# Sensor_Board.net
KiCad netlist of a schematic drawn in EAGLE
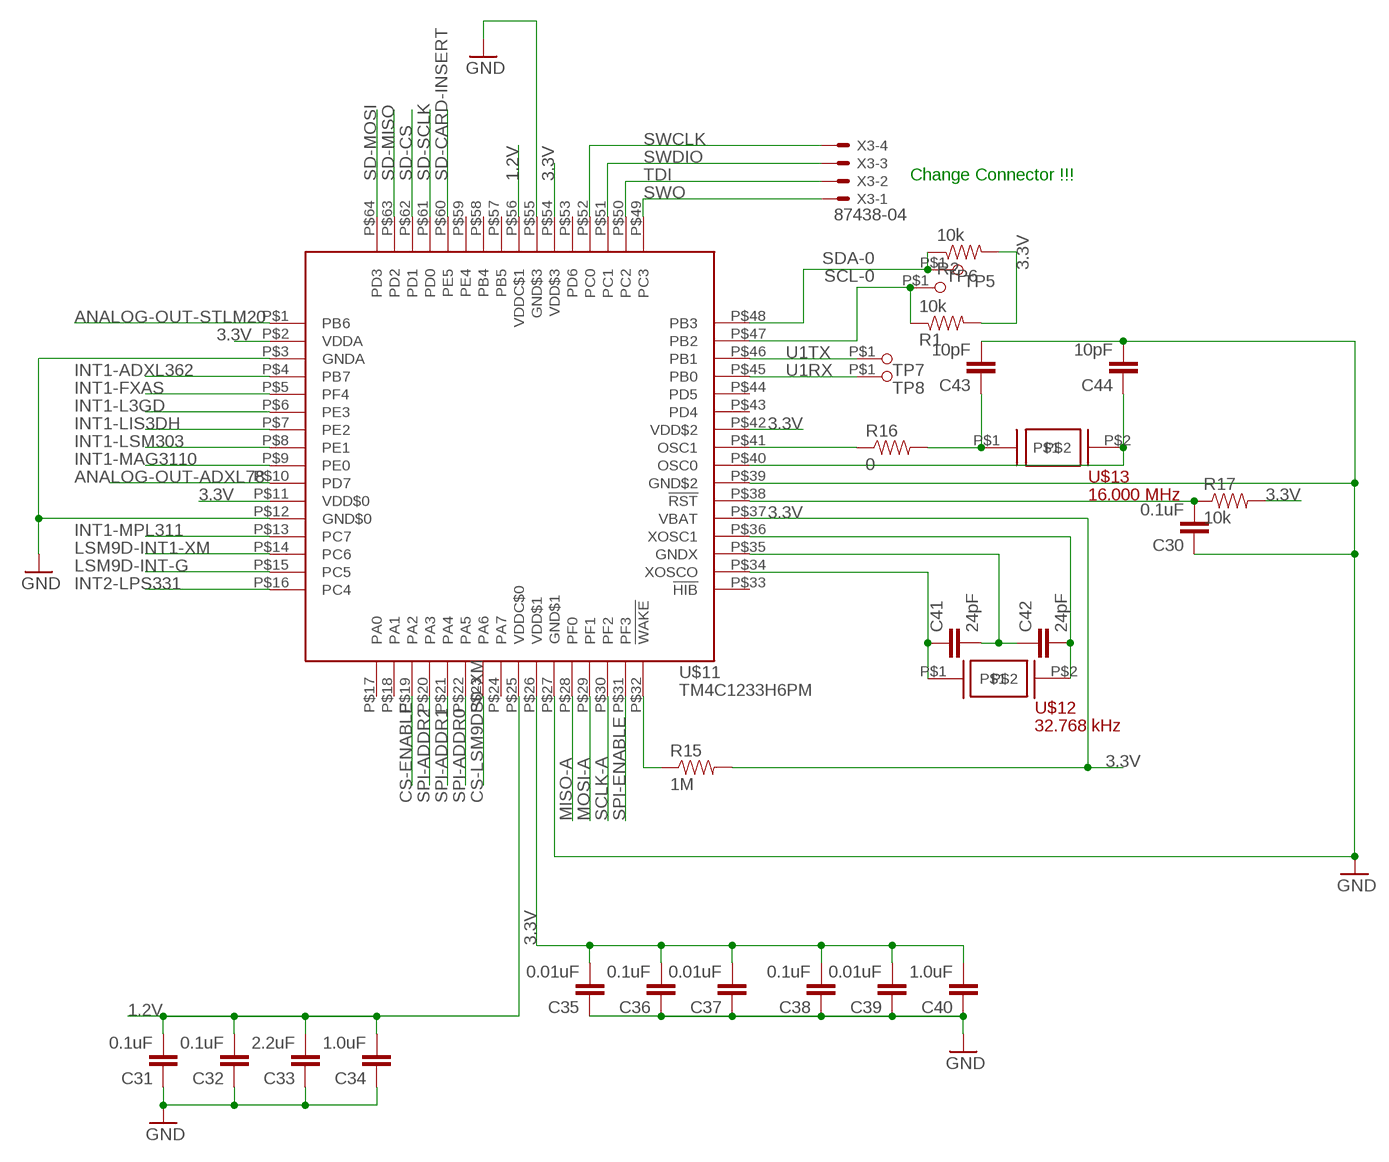
[diagram p0: schematic, sheet 1]
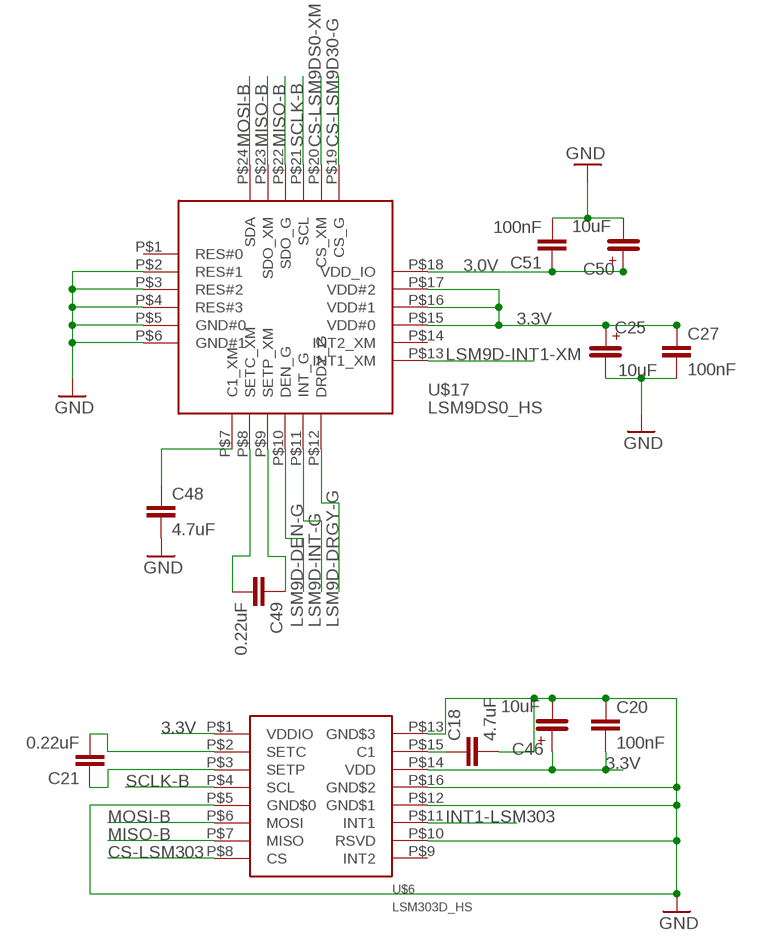
[diagram p1: schematic, sheet 2]
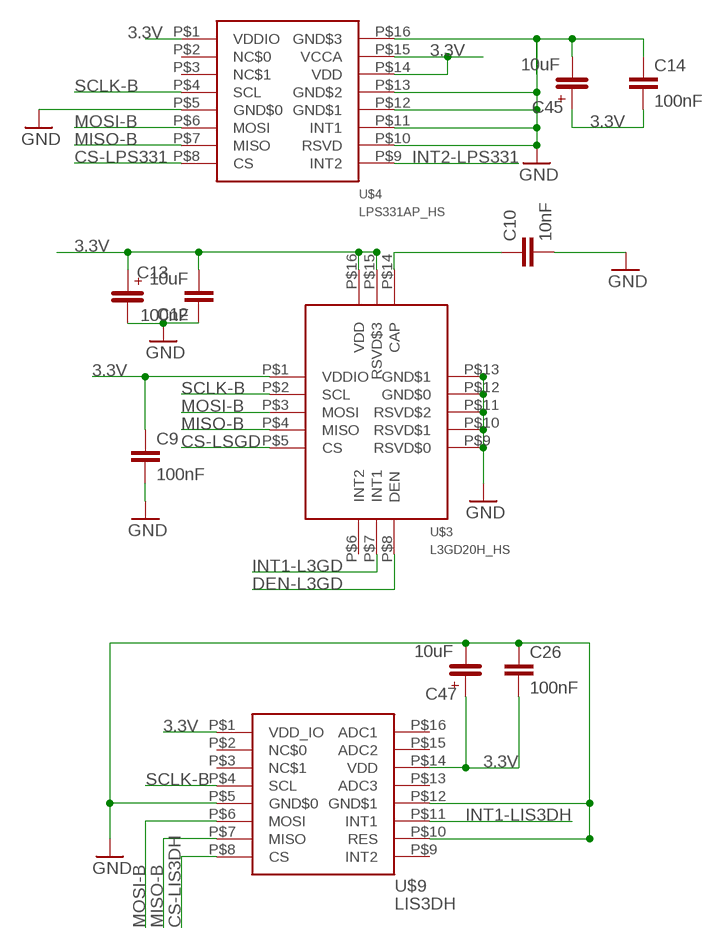
[diagram p2: schematic, sheet 3]
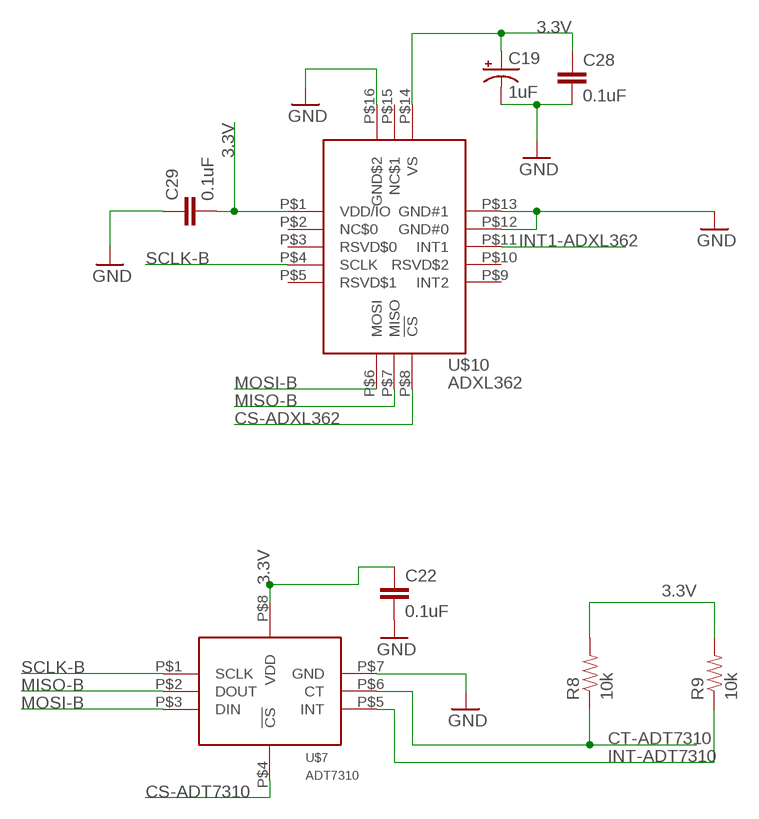
[diagram p3: schematic, sheet 4]
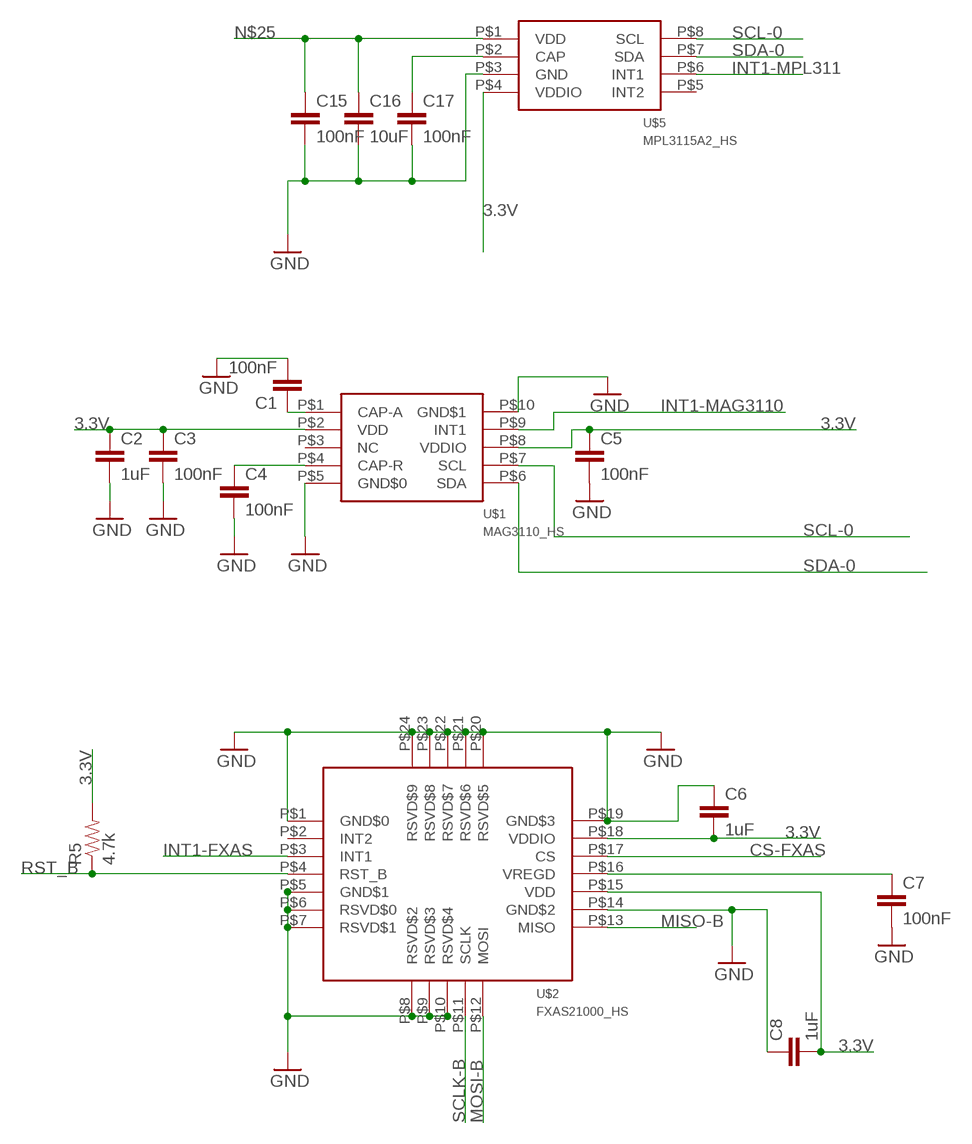
[diagram p4: schematic, sheet 5]
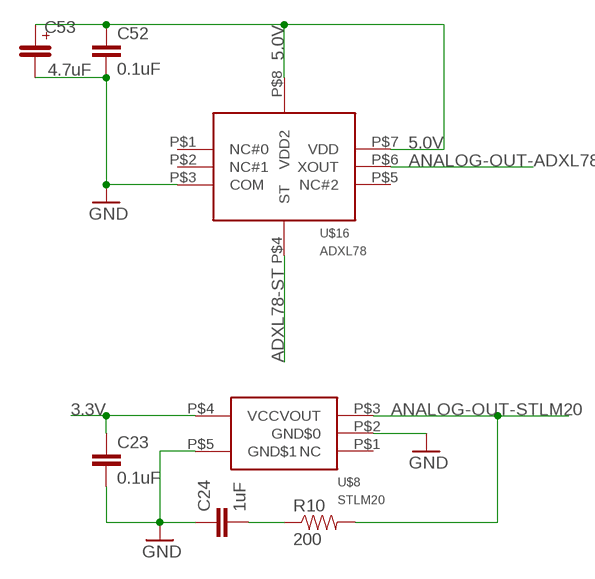
[diagram p5: schematic, sheet 6]
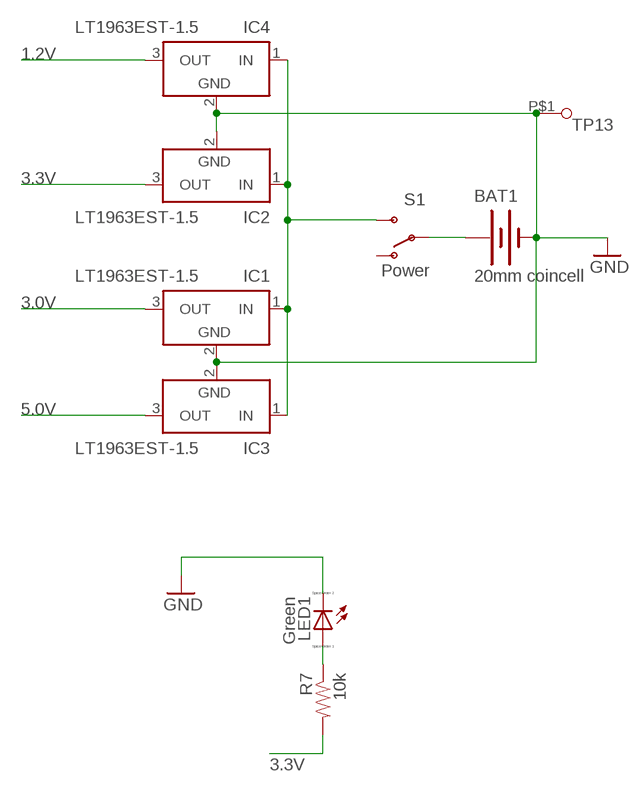
[diagram p6: schematic, sheet 7]
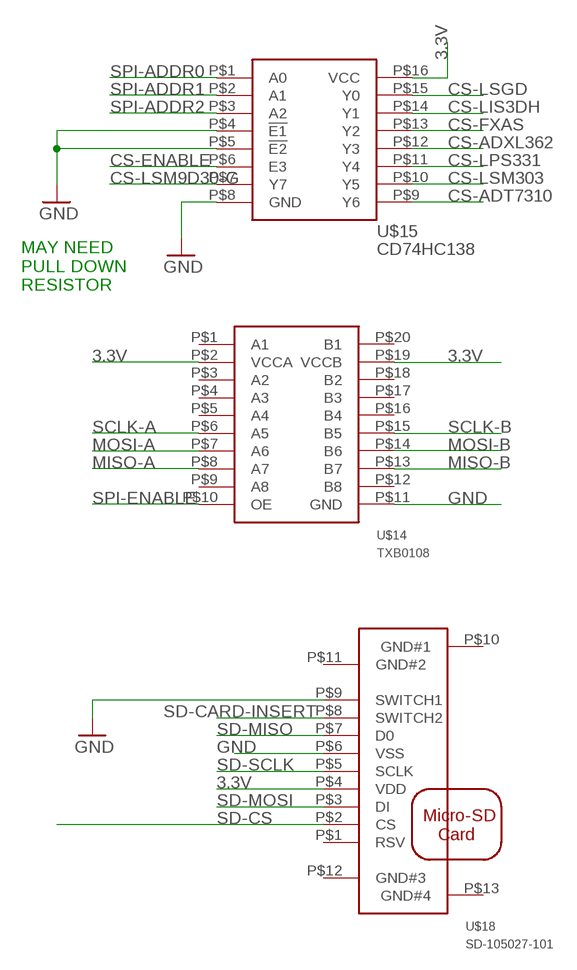
[diagram p7: schematic, sheet 8]

(export (version "E")
  (design (tool "Eeschema 10.0.6"))
  (components
    (comp (ref "C9")
      (value "100nF")
      (footprint "eagle-import:0402-CAP")
      (libsource (lib "eagle-import") (part "CAPACITOR"))
    )
    (comp (ref "C10")
      (value "10nF")
      (footprint "eagle-import:0402-CAP")
      (libsource (lib "eagle-import") (part "CAPACITOR"))
    )
    (comp (ref "C12")
      (value "10uF")
      (footprint "eagle-import:0402-CAP")
      (libsource (lib "eagle-import") (part "CAPACITOR"))
    )
    (comp (ref "C13")
      (value "100nF")
      (footprint "eagle-import:4.3X7.3SMD")
      (libsource (lib "eagle-import") (part "EEFCD0J100ER"))
    )
    (comp (ref "C14")
      (value "100nF")
      (footprint "eagle-import:0402-CAP")
      (libsource (lib "eagle-import") (part "CAPACITOR"))
    )
    (comp (ref "C26")
      (value "100nF")
      (footprint "eagle-import:0402-CAP")
      (libsource (lib "eagle-import") (part "CAPACITOR"))
    )
    (comp (ref "C45")
      (value "10uF")
      (footprint "eagle-import:4.3X7.3SMD")
      (libsource (lib "eagle-import") (part "EEFCD0J100ER"))
    )
    (comp (ref "C47")
      (value "10uF")
      (footprint "eagle-import:4.3X7.3SMD")
      (libsource (lib "eagle-import") (part "EEFCD0J100ER"))
    )
    (comp (ref "U$3")
      (value "L3GD20H_HS")
      (footprint "eagle-import:LGA-16(3X3)_HS")
      (libsource (lib "eagle-import") (part "L3GD20H_HS"))
    )
    (comp (ref "U$4")
      (value "LPS331AP_HS")
      (footprint "eagle-import:LGA-16(3X3)_HS")
      (libsource (lib "eagle-import") (part "LPS331AP_HS"))
    )
    (comp (ref "U$9")
      (value "LIS3DH")
      (footprint "eagle-import:LGA-16(3X3)_HS")
      (libsource (lib "eagle-import") (part "LIS3DH_HS"))
    )
    (comp (ref "BAT1")
      (value "20mm coincell")
      (footprint "eagle-import:BATTCON_20MM_4LEGS")
      (libsource (lib "eagle-import") (part "BATTERY20MM_4LEGS"))
    )
    (comp (ref "IC1")
      (value "LT1963EST-1.5")
      (footprint "eagle-import:SOT223")
      (libsource (lib "eagle-import") (part "LT1963EST-1.5"))
    )
    (comp (ref "IC2")
      (value "LT1963EST-1.5")
      (footprint "eagle-import:SOT223")
      (libsource (lib "eagle-import") (part "LT1963EST-1.5"))
    )
    (comp (ref "IC3")
      (value "LT1963EST-1.5")
      (footprint "eagle-import:SOT223")
      (libsource (lib "eagle-import") (part "LT1963EST-1.5"))
    )
    (comp (ref "IC4")
      (value "LT1963EST-1.5")
      (footprint "eagle-import:SOT223")
      (libsource (lib "eagle-import") (part "LT1963EST-1.5"))
    )
    (comp (ref "LED1")
      (value "Green")
      (footprint "eagle-import:LED_SML0603")
      (libsource (lib "eagle-import") (part "LED_ESML0603"))
    )
    (comp (ref "R7")
      (value "10k")
      (footprint "eagle-import:0402")
      (libsource (lib "eagle-import") (part "RESISTOR"))
    )
    (comp (ref "S1")
      (value "Power")
      (footprint "eagle-import:SWITCH-SPST-SMD-A")
      (libsource (lib "eagle-import") (part "SWITCH-SPDT-SMD-A"))
    )
    (comp (ref "TP13")
      (value "TESTPAD(ROUND)")
      (footprint "eagle-import:TESTPAD(ROUND)")
      (libsource (lib "eagle-import") (part "TESTPAD(ROUND)"))
    )
    (comp (ref "C19")
      (value "1uF")
      (footprint "eagle-import:EIA6032")
      (libsource (lib "eagle-import") (part "CAP_POL6032"))
    )
    (comp (ref "C22")
      (value "0.1uF")
      (footprint "eagle-import:0402-CAP")
      (libsource (lib "eagle-import") (part "CAPACITOR"))
    )
    (comp (ref "C28")
      (value "0.1uF")
      (footprint "eagle-import:0402-CAP")
      (libsource (lib "eagle-import") (part "CAPACITOR"))
    )
    (comp (ref "C29")
      (value "0.1uF")
      (footprint "eagle-import:0402-CAP")
      (libsource (lib "eagle-import") (part "CAPACITOR"))
    )
    (comp (ref "R8")
      (value "10k")
      (footprint "eagle-import:0402")
      (libsource (lib "eagle-import") (part "RESISTOR"))
    )
    (comp (ref "R9")
      (value "10k")
      (footprint "eagle-import:0402")
      (libsource (lib "eagle-import") (part "RESISTOR"))
    )
    (comp (ref "U$7")
      (value "ADT7310")
      (footprint "eagle-import:SOIC-8(5X6.2)")
      (libsource (lib "eagle-import") (part "ADT7310"))
    )
    (comp (ref "U$10")
      (value "ADXL362")
      (footprint "eagle-import:LGA-16(3X3.25)_HS")
      (libsource (lib "eagle-import") (part "ADXL362_HS"))
    )
    (comp (ref "C30")
      (value "0.1uF")
      (footprint "eagle-import:0402-CAP")
      (libsource (lib "eagle-import") (part "CAPACITOR"))
    )
    (comp (ref "C31")
      (value "0.1uF")
      (footprint "eagle-import:0402-CAP")
      (libsource (lib "eagle-import") (part "CAPACITOR"))
    )
    (comp (ref "C32")
      (value "0.1uF")
      (footprint "eagle-import:0402-CAP")
      (libsource (lib "eagle-import") (part "CAPACITOR"))
    )
    (comp (ref "C33")
      (value "2.2uF")
      (footprint "eagle-import:0402-CAP")
      (libsource (lib "eagle-import") (part "CAPACITOR"))
    )
    (comp (ref "C34")
      (value "1.0uF")
      (footprint "eagle-import:0402-CAP")
      (libsource (lib "eagle-import") (part "CAPACITOR"))
    )
    (comp (ref "C35")
      (value "0.01uF")
      (footprint "eagle-import:0402-CAP")
      (libsource (lib "eagle-import") (part "CAPACITOR"))
    )
    (comp (ref "C36")
      (value "0.1uF")
      (footprint "eagle-import:0402-CAP")
      (libsource (lib "eagle-import") (part "CAPACITOR"))
    )
    (comp (ref "C37")
      (value "0.01uF")
      (footprint "eagle-import:0402-CAP")
      (libsource (lib "eagle-import") (part "CAPACITOR"))
    )
    (comp (ref "C38")
      (value "0.1uF")
      (footprint "eagle-import:0402-CAP")
      (libsource (lib "eagle-import") (part "CAPACITOR"))
    )
    (comp (ref "C39")
      (value "0.01uF")
      (footprint "eagle-import:0402-CAP")
      (libsource (lib "eagle-import") (part "CAPACITOR"))
    )
    (comp (ref "C40")
      (value "1.0uF")
      (footprint "eagle-import:0402-CAP")
      (libsource (lib "eagle-import") (part "CAPACITOR"))
    )
    (comp (ref "C41")
      (value "24pF")
      (footprint "eagle-import:0402-CAP")
      (libsource (lib "eagle-import") (part "CAPACITOR"))
    )
    (comp (ref "C42")
      (value "24pF")
      (footprint "eagle-import:0402-CAP")
      (libsource (lib "eagle-import") (part "CAPACITOR"))
    )
    (comp (ref "C43")
      (value "10pF")
      (footprint "eagle-import:0402-CAP")
      (libsource (lib "eagle-import") (part "CAPACITOR"))
    )
    (comp (ref "C44")
      (value "10pF")
      (footprint "eagle-import:0402-CAP")
      (libsource (lib "eagle-import") (part "CAPACITOR"))
    )
    (comp (ref "R1")
      (value "10k")
      (footprint "eagle-import:0402")
      (libsource (lib "eagle-import") (part "RESISTOR"))
    )
    (comp (ref "R2")
      (value "10k")
      (footprint "eagle-import:0402")
      (libsource (lib "eagle-import") (part "RESISTOR"))
    )
    (comp (ref "R15")
      (value "1M")
      (footprint "eagle-import:0402")
      (libsource (lib "eagle-import") (part "RESISTOR"))
    )
    (comp (ref "R16")
      (value "0")
      (footprint "eagle-import:0402")
      (libsource (lib "eagle-import") (part "RESISTOR"))
    )
    (comp (ref "R17")
      (value "10k")
      (footprint "eagle-import:0402")
      (libsource (lib "eagle-import") (part "RESISTOR"))
    )
    (comp (ref "TP5")
      (value "TESTPAD(ROUND)")
      (footprint "eagle-import:TESTPAD(ROUND)")
      (libsource (lib "eagle-import") (part "TESTPAD(ROUND)"))
    )
    (comp (ref "TP6")
      (value "TESTPAD(ROUND)")
      (footprint "eagle-import:TESTPAD(ROUND)")
      (libsource (lib "eagle-import") (part "TESTPAD(ROUND)"))
    )
    (comp (ref "TP7")
      (value "TESTPAD(ROUND)")
      (footprint "eagle-import:TESTPAD(ROUND)")
      (libsource (lib "eagle-import") (part "TESTPAD(ROUND)"))
    )
    (comp (ref "TP8")
      (value "TESTPAD(ROUND)")
      (footprint "eagle-import:TESTPAD(ROUND)")
      (libsource (lib "eagle-import") (part "TESTPAD(ROUND)"))
    )
    (comp (ref "U$11")
      (value "TM4C1233H6PM")
      (footprint "eagle-import:S-PQFP-G64")
      (libsource (lib "eagle-import") (part "TM4C1233H6PM"))
    )
    (comp (ref "U$12")
      (value "32.768 kHz")
      (footprint "eagle-import:CYLINDRICAL-(1.9DIAX6L)")
      (libsource (lib "eagle-import") (part "AB26TRB"))
    )
    (comp (ref "U$13")
      (value "16.000 MHz")
      (footprint "eagle-import:2-SMD")
      (libsource (lib "eagle-import") (part "NX5032GA"))
    )
    (comp (ref "X3")
      (value "87438-04")
      (footprint "eagle-import:87438-04")
      (libsource (lib "eagle-import") (part "87438-04"))
    )
    (comp (ref "C18")
      (value "4.7uF")
      (footprint "eagle-import:0402-CAP")
      (libsource (lib "eagle-import") (part "CAPACITOR"))
    )
    (comp (ref "C20")
      (value "100nF")
      (footprint "eagle-import:0402-CAP")
      (libsource (lib "eagle-import") (part "CAPACITOR"))
    )
    (comp (ref "C21")
      (value "0.22uF")
      (footprint "eagle-import:0402-CAP")
      (libsource (lib "eagle-import") (part "CAPACITOR"))
    )
    (comp (ref "C25")
      (value "10uF")
      (footprint "eagle-import:4.3X7.3SMD")
      (libsource (lib "eagle-import") (part "EEFCD0J100ER"))
    )
    (comp (ref "C27")
      (value "100nF")
      (footprint "eagle-import:0402-CAP")
      (libsource (lib "eagle-import") (part "CAPACITOR"))
    )
    (comp (ref "C46")
      (value "10uF")
      (footprint "eagle-import:4.3X7.3SMD")
      (libsource (lib "eagle-import") (part "EEFCD0J100ER"))
    )
    (comp (ref "C48")
      (value "4.7uF")
      (footprint "eagle-import:0402-CAP")
      (libsource (lib "eagle-import") (part "CAPACITOR"))
    )
    (comp (ref "C49")
      (value "0.22uF")
      (footprint "eagle-import:0402-CAP")
      (libsource (lib "eagle-import") (part "CAPACITOR"))
    )
    (comp (ref "C50")
      (value "10uF")
      (footprint "eagle-import:4.3X7.3SMD")
      (libsource (lib "eagle-import") (part "EEFCD0J100ER"))
    )
    (comp (ref "C51")
      (value "100nF")
      (footprint "eagle-import:0402-CAP")
      (libsource (lib "eagle-import") (part "CAPACITOR"))
    )
    (comp (ref "U$6")
      (value "LSM303D_HS")
      (footprint "eagle-import:LGA-16(3X3)_HS")
      (libsource (lib "eagle-import") (part "LSM303D_HS"))
    )
    (comp (ref "U$17")
      (value "LSM9DS0_HS")
      (footprint "eagle-import:LGA-24(4X4)_HS")
      (libsource (lib "eagle-import") (part "LSM9DS0_HS"))
    )
    (comp (ref "C23")
      (value "0.1uF")
      (footprint "eagle-import:0402-CAP")
      (libsource (lib "eagle-import") (part "CAPACITOR"))
    )
    (comp (ref "C24")
      (value "1uF")
      (footprint "eagle-import:0402-CAP")
      (libsource (lib "eagle-import") (part "CAPACITOR"))
    )
    (comp (ref "C52")
      (value "0.1uF")
      (footprint "eagle-import:0402-CAP")
      (libsource (lib "eagle-import") (part "CAPACITOR"))
    )
    (comp (ref "C53")
      (value "4.7uF")
      (footprint "eagle-import:4.3X7.3SMD")
      (libsource (lib "eagle-import") (part "EEFCD0J100ER"))
    )
    (comp (ref "R10")
      (value "200")
      (footprint "eagle-import:0402")
      (libsource (lib "eagle-import") (part "RESISTOR"))
    )
    (comp (ref "U$8")
      (value "STLM20")
      (footprint "eagle-import:SOT323-5L")
      (libsource (lib "eagle-import") (part "STLM20"))
    )
    (comp (ref "U$16")
      (value "ADXL78")
      (footprint "eagle-import:LCC-8(5X5)_HS")
      (libsource (lib "eagle-import") (part "ADXL78"))
    )
    (comp (ref "C1")
      (value "100nF")
      (footprint "eagle-import:0402-CAP")
      (libsource (lib "eagle-import") (part "CAPACITOR"))
    )
    (comp (ref "C2")
      (value "1uF")
      (footprint "eagle-import:0402-CAP")
      (libsource (lib "eagle-import") (part "CAPACITOR"))
    )
    (comp (ref "C3")
      (value "100nF")
      (footprint "eagle-import:0402-CAP")
      (libsource (lib "eagle-import") (part "CAPACITOR"))
    )
    (comp (ref "C4")
      (value "100nF")
      (footprint "eagle-import:0402-CAP")
      (libsource (lib "eagle-import") (part "CAPACITOR"))
    )
    (comp (ref "C5")
      (value "100nF")
      (footprint "eagle-import:0402-CAP")
      (libsource (lib "eagle-import") (part "CAPACITOR"))
    )
    (comp (ref "C6")
      (value "1uF")
      (footprint "eagle-import:0402-CAP")
      (libsource (lib "eagle-import") (part "CAPACITOR"))
    )
    (comp (ref "C7")
      (value "100nF")
      (footprint "eagle-import:0402-CAP")
      (libsource (lib "eagle-import") (part "CAPACITOR"))
    )
    (comp (ref "C8")
      (value "1uF")
      (footprint "eagle-import:0402-CAP")
      (libsource (lib "eagle-import") (part "CAPACITOR"))
    )
    (comp (ref "C15")
      (value "100nF")
      (footprint "eagle-import:0402-CAP")
      (libsource (lib "eagle-import") (part "CAPACITOR"))
    )
    (comp (ref "C16")
      (value "10uF")
      (footprint "eagle-import:0402-CAP")
      (libsource (lib "eagle-import") (part "CAPACITOR"))
    )
    (comp (ref "C17")
      (value "100nF")
      (footprint "eagle-import:0402-CAP")
      (libsource (lib "eagle-import") (part "CAPACITOR"))
    )
    (comp (ref "R5")
      (value "4.7k")
      (footprint "eagle-import:0402")
      (libsource (lib "eagle-import") (part "RESISTOR"))
    )
    (comp (ref "U$1")
      (value "MAG3110_HS")
      (footprint "eagle-import:DFN-10(2X2)_HS")
      (libsource (lib "eagle-import") (part "MAG3110_HS"))
    )
    (comp (ref "U$2")
      (value "FXAS21000_HS")
      (footprint "eagle-import:QFN-24(4X4)_HS")
      (libsource (lib "eagle-import") (part "FXAS21000_HS"))
    )
    (comp (ref "U$5")
      (value "MPL3115A2_HS")
      (footprint "eagle-import:LGA-8(5X3)_HS")
      (libsource (lib "eagle-import") (part "MPL3115A2_HS"))
    )
    (comp (ref "U$14")
      (value "TXB0108")
      (footprint "eagle-import:TSSOP-(PW)-20")
      (libsource (lib "eagle-import") (part "TXB0108"))
    )
    (comp (ref "U$15")
      (value "CD74HC138")
      (footprint "eagle-import:SOIC-16")
      (libsource (lib "eagle-import") (part "CD74HC138"))
    )
    (comp (ref "U$18")
      (value "SD-105027-101")
      (footprint "eagle-import:SD-105027-101")
      (libsource (lib "eagle-import") (part "SD-105027-101"))
    )
  )
  (nets
    (net (code "1") (name "1.2V") (class "Default")
      (node (ref "C31") (pin "2") (pinfunction "2_2") (pintype "passive"))
      (node (ref "C32") (pin "2") (pinfunction "2_2") (pintype "passive"))
      (node (ref "C33") (pin "2") (pinfunction "2_2") (pintype "passive"))
      (node (ref "C34") (pin "2") (pinfunction "2_2") (pintype "passive"))
      (node (ref "IC4") (pin "3") (pinfunction "OUT_3") (pintype "output"))
      (node (ref "U$11") (pin "P$25") (pinfunction "VDDC$0_P$25") (pintype "bidirectional"))
      (node (ref "U$11") (pin "P$56") (pinfunction "VDDC$1_P$56") (pintype "bidirectional"))
    )
    (net (code "2") (name "3.0V") (class "Default")
      (node (ref "C50") (pin "P$1") (pintype "bidirectional"))
      (node (ref "C51") (pin "1") (pinfunction "1_1") (pintype "passive"))
      (node (ref "IC1") (pin "3") (pinfunction "OUT_3") (pintype "output"))
      (node (ref "U$17") (pin "P$18") (pinfunction "VDD_IO_P$18") (pintype "bidirectional"))
    )
    (net (code "3") (name "3.3V") (class "Default")
      (node (ref "C12") (pin "2") (pinfunction "2_2") (pintype "passive"))
      (node (ref "C13") (pin "P$1") (pintype "bidirectional"))
      (node (ref "C14") (pin "2") (pinfunction "2_2") (pintype "passive"))
      (node (ref "C19") (pin "P$1") (pinfunction "+_P$1") (pintype "passive"))
      (node (ref "C2") (pin "1") (pinfunction "1_1") (pintype "passive"))
      (node (ref "C20") (pin "2") (pinfunction "2_2") (pintype "passive"))
      (node (ref "C22") (pin "1") (pinfunction "1_1") (pintype "passive"))
      (node (ref "C23") (pin "1") (pinfunction "1_1") (pintype "passive"))
      (node (ref "C25") (pin "P$1") (pintype "bidirectional"))
      (node (ref "C26") (pin "2") (pinfunction "2_2") (pintype "passive"))
      (node (ref "C27") (pin "1") (pinfunction "1_1") (pintype "passive"))
      (node (ref "C28") (pin "1") (pinfunction "1_1") (pintype "passive"))
      (node (ref "C29") (pin "2") (pinfunction "2_2") (pintype "passive"))
      (node (ref "C3") (pin "1") (pinfunction "1_1") (pintype "passive"))
      (node (ref "C35") (pin "2") (pinfunction "2_2") (pintype "passive"))
      (node (ref "C36") (pin "2") (pinfunction "2_2") (pintype "passive"))
      (node (ref "C37") (pin "2") (pinfunction "2_2") (pintype "passive"))
      (node (ref "C38") (pin "2") (pinfunction "2_2") (pintype "passive"))
      (node (ref "C39") (pin "2") (pinfunction "2_2") (pintype "passive"))
      (node (ref "C40") (pin "2") (pinfunction "2_2") (pintype "passive"))
      (node (ref "C45") (pin "P$1") (pintype "bidirectional"))
      (node (ref "C46") (pin "P$1") (pintype "bidirectional"))
      (node (ref "C47") (pin "P$1") (pintype "bidirectional"))
      (node (ref "C5") (pin "1") (pinfunction "1_1") (pintype "passive"))
      (node (ref "C6") (pin "2") (pinfunction "2_2") (pintype "passive"))
      (node (ref "C8") (pin "2") (pinfunction "2_2") (pintype "passive"))
      (node (ref "C9") (pin "1") (pinfunction "1_1") (pintype "passive"))
      (node (ref "IC2") (pin "3") (pinfunction "OUT_3") (pintype "output"))
      (node (ref "R1") (pin "2") (pinfunction "2_2") (pintype "passive"))
      (node (ref "R15") (pin "2") (pinfunction "2_2") (pintype "passive"))
      (node (ref "R17") (pin "2") (pinfunction "2_2") (pintype "passive"))
      (node (ref "R2") (pin "2") (pinfunction "2_2") (pintype "passive"))
      (node (ref "R5") (pin "2") (pinfunction "2_2") (pintype "passive"))
      (node (ref "R7") (pin "2") (pinfunction "2_2") (pintype "passive"))
      (node (ref "R8") (pin "2") (pinfunction "2_2") (pintype "passive"))
      (node (ref "R9") (pin "2") (pinfunction "2_2") (pintype "passive"))
      (node (ref "U$1") (pin "P$2") (pinfunction "VDD_P$2") (pintype "bidirectional"))
      (node (ref "U$1") (pin "P$8") (pinfunction "VDDIO_P$8") (pintype "bidirectional"))
      (node (ref "U$10") (pin "P$1") (pinfunction "VDD/IO_P$1") (pintype "bidirectional"))
      (node (ref "U$10") (pin "P$14") (pinfunction "VS_P$14") (pintype "bidirectional"))
      (node (ref "U$11") (pin "P$11") (pinfunction "VDD$0_P$11") (pintype "bidirectional"))
      (node (ref "U$11") (pin "P$2") (pinfunction "VDDA_P$2") (pintype "bidirectional"))
      (node (ref "U$11") (pin "P$26") (pinfunction "VDD$1_P$26") (pintype "bidirectional"))
      (node (ref "U$11") (pin "P$37") (pinfunction "VBAT_P$37") (pintype "bidirectional"))
      (node (ref "U$11") (pin "P$42") (pinfunction "VDD$2_P$42") (pintype "bidirectional"))
      (node (ref "U$11") (pin "P$54") (pinfunction "VDD$3_P$54") (pintype "bidirectional"))
      (node (ref "U$14") (pin "P$19") (pinfunction "VCCB_P$19") (pintype "bidirectional"))
      (node (ref "U$14") (pin "P$2") (pinfunction "VCCA_P$2") (pintype "bidirectional"))
      (node (ref "U$15") (pin "P$16") (pinfunction "VCC_P$16") (pintype "bidirectional"))
      (node (ref "U$17") (pin "P$15") (pinfunction "VDD#0_P$15") (pintype "bidirectional"))
      (node (ref "U$17") (pin "P$16") (pinfunction "VDD#1_P$16") (pintype "bidirectional"))
      (node (ref "U$17") (pin "P$17") (pinfunction "VDD#2_P$17") (pintype "bidirectional"))
      (node (ref "U$18") (pin "P$4") (pinfunction "VDD_P$4") (pintype "bidirectional"))
      (node (ref "U$2") (pin "P$15") (pinfunction "VDD_P$15") (pintype "bidirectional"))
      (node (ref "U$2") (pin "P$18") (pinfunction "VDDIO_P$18") (pintype "bidirectional"))
      (node (ref "U$3") (pin "P$1") (pinfunction "VDDIO_P$1") (pintype "bidirectional"))
      (node (ref "U$3") (pin "P$15") (pinfunction "RSVD$3_P$15") (pintype "bidirectional"))
      (node (ref "U$3") (pin "P$16") (pinfunction "VDD_P$16") (pintype "bidirectional"))
      (node (ref "U$4") (pin "P$1") (pinfunction "VDDIO_P$1") (pintype "bidirectional"))
      (node (ref "U$4") (pin "P$14") (pinfunction "VDD_P$14") (pintype "bidirectional"))
      (node (ref "U$4") (pin "P$15") (pinfunction "VCCA_P$15") (pintype "bidirectional"))
      (node (ref "U$5") (pin "P$4") (pinfunction "VDDIO_P$4") (pintype "bidirectional"))
      (node (ref "U$6") (pin "P$1") (pinfunction "VDDIO_P$1") (pintype "bidirectional"))
      (node (ref "U$6") (pin "P$14") (pinfunction "VDD_P$14") (pintype "bidirectional"))
      (node (ref "U$7") (pin "P$8") (pinfunction "VDD_P$8") (pintype "bidirectional"))
      (node (ref "U$8") (pin "P$4") (pinfunction "VCC_P$4") (pintype "bidirectional"))
      (node (ref "U$9") (pin "P$1") (pinfunction "VDD_IO_P$1") (pintype "bidirectional"))
      (node (ref "U$9") (pin "P$14") (pinfunction "VDD_P$14") (pintype "bidirectional"))
    )
    (net (code "4") (name "5.0V") (class "Default")
      (node (ref "C52") (pin "1") (pinfunction "1_1") (pintype "passive"))
      (node (ref "C53") (pin "P$1") (pintype "bidirectional"))
      (node (ref "IC3") (pin "3") (pinfunction "OUT_3") (pintype "output"))
      (node (ref "U$16") (pin "P$7") (pinfunction "VDD_P$7") (pintype "bidirectional"))
      (node (ref "U$16") (pin "P$8") (pinfunction "VDD2_P$8") (pintype "bidirectional"))
    )
    (net (code "5") (name "ADXL78-ST") (class "Default")
      (node (ref "U$16") (pin "P$4") (pinfunction "ST_P$4") (pintype "bidirectional"))
    )
    (net (code "6") (name "ANALOG-OUT-ADXL78") (class "Default")
      (node (ref "U$11") (pin "P$10") (pinfunction "PD7_P$10") (pintype "bidirectional"))
      (node (ref "U$16") (pin "P$6") (pinfunction "XOUT_P$6") (pintype "bidirectional"))
    )
    (net (code "7") (name "ANALOG-OUT-STLM20") (class "Default")
      (node (ref "R10") (pin "2") (pinfunction "2_2") (pintype "passive"))
      (node (ref "U$11") (pin "P$1") (pinfunction "PB6_P$1") (pintype "bidirectional"))
      (node (ref "U$8") (pin "P$3") (pinfunction "VOUT_P$3") (pintype "bidirectional"))
    )
    (net (code "8") (name "CS-ADT7310") (class "Default")
      (node (ref "U$15") (pin "P$9") (pinfunction "Y6_P$9") (pintype "bidirectional"))
      (node (ref "U$7") (pin "P$4") (pinfunction "~{CS}_P$4") (pintype "bidirectional"))
    )
    (net (code "9") (name "CS-ADXL362") (class "Default")
      (node (ref "U$10") (pin "P$8") (pinfunction "~{CS}_P$8") (pintype "bidirectional"))
      (node (ref "U$15") (pin "P$12") (pinfunction "Y3_P$12") (pintype "bidirectional"))
    )
    (net (code "10") (name "CS-ENABLE") (class "Default")
      (node (ref "U$11") (pin "P$19") (pinfunction "PA2_P$19") (pintype "bidirectional"))
      (node (ref "U$15") (pin "P$6") (pinfunction "E3_P$6") (pintype "bidirectional"))
    )
    (net (code "11") (name "CS-FXAS") (class "Default")
      (node (ref "U$15") (pin "P$13") (pinfunction "Y2_P$13") (pintype "bidirectional"))
      (node (ref "U$2") (pin "P$17") (pinfunction "CS_P$17") (pintype "bidirectional"))
    )
    (net (code "12") (name "CS-LIS3DH") (class "Default")
      (node (ref "U$15") (pin "P$14") (pinfunction "Y1_P$14") (pintype "bidirectional"))
      (node (ref "U$9") (pin "P$8") (pinfunction "CS_P$8") (pintype "bidirectional"))
    )
    (net (code "13") (name "CS-LPS331") (class "Default")
      (node (ref "U$15") (pin "P$11") (pinfunction "Y4_P$11") (pintype "bidirectional"))
      (node (ref "U$4") (pin "P$8") (pinfunction "CS_P$8") (pintype "bidirectional"))
    )
    (net (code "14") (name "CS-LSGD") (class "Default")
      (node (ref "U$15") (pin "P$15") (pinfunction "Y0_P$15") (pintype "bidirectional"))
      (node (ref "U$3") (pin "P$5") (pinfunction "CS_P$5") (pintype "bidirectional"))
    )
    (net (code "15") (name "CS-LSM9D30-G") (class "Default")
      (node (ref "U$15") (pin "P$7") (pinfunction "Y7_P$7") (pintype "bidirectional"))
      (node (ref "U$17") (pin "P$19") (pinfunction "CS_G_P$19") (pintype "bidirectional"))
    )
    (net (code "16") (name "CS-LSM9DS0-XM") (class "Default")
      (node (ref "U$11") (pin "P$23") (pinfunction "PA6_P$23") (pintype "bidirectional"))
      (node (ref "U$17") (pin "P$20") (pinfunction "CS_XM_P$20") (pintype "bidirectional"))
    )
    (net (code "17") (name "CS-LSM303") (class "Default")
      (node (ref "U$15") (pin "P$10") (pinfunction "Y5_P$10") (pintype "bidirectional"))
      (node (ref "U$6") (pin "P$8") (pinfunction "CS_P$8") (pintype "bidirectional"))
    )
    (net (code "18") (name "CT-ADT7310") (class "Default")
      (node (ref "R8") (pin "1") (pinfunction "1_1") (pintype "passive"))
      (node (ref "U$7") (pin "P$6") (pinfunction "CT_P$6") (pintype "bidirectional"))
    )
    (net (code "19") (name "DEN-L3GD") (class "Default")
      (node (ref "U$3") (pin "P$8") (pinfunction "DEN_P$8") (pintype "bidirectional"))
    )
    (net (code "20") (name "GND") (class "Default")
      (node (ref "BAT1") (pin "2") (pinfunction "-_2") (pintype "power_in"))
      (node (ref "C1") (pin "2") (pinfunction "2_2") (pintype "passive"))
      (node (ref "C10") (pin "2") (pinfunction "2_2") (pintype "passive"))
      (node (ref "C12") (pin "1") (pinfunction "1_1") (pintype "passive"))
      (node (ref "C13") (pin "P$2") (pintype "bidirectional"))
      (node (ref "C14") (pin "1") (pinfunction "1_1") (pintype "passive"))
      (node (ref "C15") (pin "2") (pinfunction "2_2") (pintype "passive"))
      (node (ref "C16") (pin "2") (pinfunction "2_2") (pintype "passive"))
      (node (ref "C17") (pin "2") (pinfunction "2_2") (pintype "passive"))
      (node (ref "C18") (pin "2") (pinfunction "2_2") (pintype "passive"))
      (node (ref "C19") (pin "P$2") (pinfunction "-_P$2") (pintype "passive"))
      (node (ref "C2") (pin "2") (pinfunction "2_2") (pintype "passive"))
      (node (ref "C20") (pin "1") (pinfunction "1_1") (pintype "passive"))
      (node (ref "C22") (pin "2") (pinfunction "2_2") (pintype "passive"))
      (node (ref "C23") (pin "2") (pinfunction "2_2") (pintype "passive"))
      (node (ref "C24") (pin "1") (pinfunction "1_1") (pintype "passive"))
      (node (ref "C25") (pin "P$2") (pintype "bidirectional"))
      (node (ref "C26") (pin "1") (pinfunction "1_1") (pintype "passive"))
      (node (ref "C27") (pin "2") (pinfunction "2_2") (pintype "passive"))
      (node (ref "C28") (pin "2") (pinfunction "2_2") (pintype "passive"))
      (node (ref "C29") (pin "1") (pinfunction "1_1") (pintype "passive"))
      (node (ref "C3") (pin "2") (pinfunction "2_2") (pintype "passive"))
      (node (ref "C30") (pin "1") (pinfunction "1_1") (pintype "passive"))
      (node (ref "C31") (pin "1") (pinfunction "1_1") (pintype "passive"))
      (node (ref "C32") (pin "1") (pinfunction "1_1") (pintype "passive"))
      (node (ref "C33") (pin "1") (pinfunction "1_1") (pintype "passive"))
      (node (ref "C34") (pin "1") (pinfunction "1_1") (pintype "passive"))
      (node (ref "C35") (pin "1") (pinfunction "1_1") (pintype "passive"))
      (node (ref "C36") (pin "1") (pinfunction "1_1") (pintype "passive"))
      (node (ref "C37") (pin "1") (pinfunction "1_1") (pintype "passive"))
      (node (ref "C38") (pin "1") (pinfunction "1_1") (pintype "passive"))
      (node (ref "C39") (pin "1") (pinfunction "1_1") (pintype "passive"))
      (node (ref "C4") (pin "2") (pinfunction "2_2") (pintype "passive"))
      (node (ref "C40") (pin "1") (pinfunction "1_1") (pintype "passive"))
      (node (ref "C43") (pin "2") (pinfunction "2_2") (pintype "passive"))
      (node (ref "C44") (pin "2") (pinfunction "2_2") (pintype "passive"))
      (node (ref "C45") (pin "P$2") (pintype "bidirectional"))
      (node (ref "C46") (pin "P$2") (pintype "bidirectional"))
      (node (ref "C47") (pin "P$2") (pintype "bidirectional"))
      (node (ref "C48") (pin "2") (pinfunction "2_2") (pintype "passive"))
      (node (ref "C5") (pin "2") (pinfunction "2_2") (pintype "passive"))
      (node (ref "C50") (pin "P$2") (pintype "bidirectional"))
      (node (ref "C51") (pin "2") (pinfunction "2_2") (pintype "passive"))
      (node (ref "C52") (pin "2") (pinfunction "2_2") (pintype "passive"))
      (node (ref "C53") (pin "P$2") (pintype "bidirectional"))
      (node (ref "C6") (pin "1") (pinfunction "1_1") (pintype "passive"))
      (node (ref "C7") (pin "2") (pinfunction "2_2") (pintype "passive"))
      (node (ref "C8") (pin "1") (pinfunction "1_1") (pintype "passive"))
      (node (ref "C9") (pin "2") (pinfunction "2_2") (pintype "passive"))
      (node (ref "IC1") (pin "2") (pinfunction "GND_2") (pintype "power_in"))
      (node (ref "IC2") (pin "2") (pinfunction "GND_2") (pintype "power_in"))
      (node (ref "IC3") (pin "2") (pinfunction "GND_2") (pintype "power_in"))
      (node (ref "IC4") (pin "2") (pinfunction "GND_2") (pintype "power_in"))
      (node (ref "LED1") (pin "C") (pinfunction "C_C") (pintype "passive"))
      (node (ref "TP13") (pin "P$1") (pinfunction "P$1_P$1") (pintype "bidirectional"))
      (node (ref "U$1") (pin "P$10") (pinfunction "GND$1_P$10") (pintype "bidirectional"))
      (node (ref "U$1") (pin "P$5") (pinfunction "GND$0_P$5") (pintype "bidirectional"))
      (node (ref "U$10") (pin "P$12") (pinfunction "GND#0_P$12") (pintype "bidirectional"))
      (node (ref "U$10") (pin "P$13") (pinfunction "GND#1_P$13") (pintype "bidirectional"))
      (node (ref "U$10") (pin "P$16") (pinfunction "GND$2_P$16") (pintype "bidirectional"))
      (node (ref "U$11") (pin "P$12") (pinfunction "GND$0_P$12") (pintype "bidirectional"))
      (node (ref "U$11") (pin "P$27") (pinfunction "GND$1_P$27") (pintype "bidirectional"))
      (node (ref "U$11") (pin "P$3") (pinfunction "GNDA_P$3") (pintype "bidirectional"))
      (node (ref "U$11") (pin "P$39") (pinfunction "GND$2_P$39") (pintype "bidirectional"))
      (node (ref "U$11") (pin "P$55") (pinfunction "GND$3_P$55") (pintype "bidirectional"))
      (node (ref "U$14") (pin "P$11") (pinfunction "GND_P$11") (pintype "bidirectional"))
      (node (ref "U$15") (pin "P$4") (pinfunction "~{E1}_P$4") (pintype "bidirectional"))
      (node (ref "U$15") (pin "P$5") (pinfunction "~{E2}_P$5") (pintype "bidirectional"))
      (node (ref "U$15") (pin "P$8") (pinfunction "GND_P$8") (pintype "bidirectional"))
      (node (ref "U$16") (pin "P$3") (pinfunction "COM_P$3") (pintype "bidirectional"))
      (node (ref "U$17") (pin "P$2") (pinfunction "RES#1_P$2") (pintype "bidirectional"))
      (node (ref "U$17") (pin "P$3") (pinfunction "RES#2_P$3") (pintype "bidirectional"))
      (node (ref "U$17") (pin "P$4") (pinfunction "RES#3_P$4") (pintype "bidirectional"))
      (node (ref "U$17") (pin "P$5") (pinfunction "GND#0_P$5") (pintype "bidirectional"))
      (node (ref "U$17") (pin "P$6") (pinfunction "GND#1_P$6") (pintype "bidirectional"))
      (node (ref "U$18") (pin "P$6") (pinfunction "VSS_P$6") (pintype "bidirectional"))
      (node (ref "U$18") (pin "P$9") (pinfunction "SWITCH1_P$9") (pintype "bidirectional"))
      (node (ref "U$2") (pin "P$1") (pinfunction "GND$0_P$1") (pintype "bidirectional"))
      (node (ref "U$2") (pin "P$10") (pinfunction "RSVD$4_P$10") (pintype "bidirectional"))
      (node (ref "U$2") (pin "P$14") (pinfunction "GND$2_P$14") (pintype "bidirectional"))
      (node (ref "U$2") (pin "P$19") (pinfunction "GND$3_P$19") (pintype "bidirectional"))
      (node (ref "U$2") (pin "P$20") (pinfunction "RSVD$5_P$20") (pintype "bidirectional"))
      (node (ref "U$2") (pin "P$21") (pinfunction "RSVD$6_P$21") (pintype "bidirectional"))
      (node (ref "U$2") (pin "P$22") (pinfunction "RSVD$7_P$22") (pintype "bidirectional"))
      (node (ref "U$2") (pin "P$23") (pinfunction "RSVD$8_P$23") (pintype "bidirectional"))
      (node (ref "U$2") (pin "P$24") (pinfunction "RSVD$9_P$24") (pintype "bidirectional"))
      (node (ref "U$2") (pin "P$5") (pinfunction "GND$1_P$5") (pintype "bidirectional"))
      (node (ref "U$2") (pin "P$6") (pinfunction "RSVD$0_P$6") (pintype "bidirectional"))
      (node (ref "U$2") (pin "P$7") (pinfunction "RSVD$1_P$7") (pintype "bidirectional"))
      (node (ref "U$2") (pin "P$8") (pinfunction "RSVD$2_P$8") (pintype "bidirectional"))
      (node (ref "U$2") (pin "P$9") (pinfunction "RSVD$3_P$9") (pintype "bidirectional"))
      (node (ref "U$3") (pin "P$10") (pinfunction "RSVD$1_P$10") (pintype "bidirectional"))
      (node (ref "U$3") (pin "P$11") (pinfunction "RSVD$2_P$11") (pintype "bidirectional"))
      (node (ref "U$3") (pin "P$12") (pinfunction "GND$0_P$12") (pintype "bidirectional"))
      (node (ref "U$3") (pin "P$13") (pinfunction "GND$1_P$13") (pintype "bidirectional"))
      (node (ref "U$3") (pin "P$9") (pinfunction "RSVD$0_P$9") (pintype "bidirectional"))
      (node (ref "U$4") (pin "P$10") (pinfunction "RSVD_P$10") (pintype "bidirectional"))
      (node (ref "U$4") (pin "P$11") (pinfunction "INT1_P$11") (pintype "bidirectional"))
      (node (ref "U$4") (pin "P$12") (pinfunction "GND$1_P$12") (pintype "bidirectional"))
      (node (ref "U$4") (pin "P$13") (pinfunction "GND$2_P$13") (pintype "bidirectional"))
      (node (ref "U$4") (pin "P$16") (pinfunction "GND$3_P$16") (pintype "bidirectional"))
      (node (ref "U$4") (pin "P$5") (pinfunction "GND$0_P$5") (pintype "bidirectional"))
      (node (ref "U$5") (pin "P$3") (pinfunction "GND_P$3") (pintype "bidirectional"))
      (node (ref "U$6") (pin "P$10") (pinfunction "RSVD_P$10") (pintype "bidirectional"))
      (node (ref "U$6") (pin "P$12") (pinfunction "GND$1_P$12") (pintype "bidirectional"))
      (node (ref "U$6") (pin "P$13") (pinfunction "GND$3_P$13") (pintype "bidirectional"))
      (node (ref "U$6") (pin "P$16") (pinfunction "GND$2_P$16") (pintype "bidirectional"))
      (node (ref "U$6") (pin "P$5") (pinfunction "GND$0_P$5") (pintype "bidirectional"))
      (node (ref "U$7") (pin "P$7") (pinfunction "GND_P$7") (pintype "bidirectional"))
      (node (ref "U$8") (pin "P$2") (pinfunction "GND$0_P$2") (pintype "bidirectional"))
      (node (ref "U$8") (pin "P$5") (pinfunction "GND$1_P$5") (pintype "bidirectional"))
      (node (ref "U$9") (pin "P$10") (pinfunction "RES_P$10") (pintype "bidirectional"))
      (node (ref "U$9") (pin "P$12") (pinfunction "GND$1_P$12") (pintype "bidirectional"))
      (node (ref "U$9") (pin "P$5") (pinfunction "GND$0_P$5") (pintype "bidirectional"))
    )
    (net (code "21") (name "INT-ADT7310") (class "Default")
      (node (ref "R9") (pin "1") (pinfunction "1_1") (pintype "passive"))
      (node (ref "U$7") (pin "P$5") (pinfunction "INT_P$5") (pintype "bidirectional"))
    )
    (net (code "22") (name "INT1-ADXL362") (class "Default")
      (node (ref "U$10") (pin "P$11") (pinfunction "INT1_P$11") (pintype "bidirectional"))
      (node (ref "U$11") (pin "P$4") (pinfunction "PB7_P$4") (pintype "bidirectional"))
    )
    (net (code "23") (name "INT1-FXAS") (class "Default")
      (node (ref "U$11") (pin "P$5") (pinfunction "PF4_P$5") (pintype "bidirectional"))
      (node (ref "U$2") (pin "P$3") (pinfunction "INT1_P$3") (pintype "bidirectional"))
    )
    (net (code "24") (name "INT1-L3GD") (class "Default")
      (node (ref "U$11") (pin "P$6") (pinfunction "PE3_P$6") (pintype "bidirectional"))
      (node (ref "U$3") (pin "P$7") (pinfunction "INT1_P$7") (pintype "bidirectional"))
    )
    (net (code "25") (name "INT1-LIS3DH") (class "Default")
      (node (ref "U$11") (pin "P$7") (pinfunction "PE2_P$7") (pintype "bidirectional"))
      (node (ref "U$9") (pin "P$11") (pinfunction "INT1_P$11") (pintype "bidirectional"))
    )
    (net (code "26") (name "INT1-LSM303") (class "Default")
      (node (ref "U$11") (pin "P$8") (pinfunction "PE1_P$8") (pintype "bidirectional"))
      (node (ref "U$6") (pin "P$11") (pinfunction "INT1_P$11") (pintype "bidirectional"))
    )
    (net (code "27") (name "INT1-MAG3110") (class "Default")
      (node (ref "U$1") (pin "P$9") (pinfunction "INT1_P$9") (pintype "bidirectional"))
      (node (ref "U$11") (pin "P$9") (pinfunction "PE0_P$9") (pintype "bidirectional"))
    )
    (net (code "28") (name "INT1-MPL311") (class "Default")
      (node (ref "U$11") (pin "P$13") (pinfunction "PC7_P$13") (pintype "bidirectional"))
      (node (ref "U$5") (pin "P$6") (pinfunction "INT1_P$6") (pintype "bidirectional"))
    )
    (net (code "29") (name "INT2-LPS331") (class "Default")
      (node (ref "U$11") (pin "P$16") (pinfunction "PC4_P$16") (pintype "bidirectional"))
      (node (ref "U$4") (pin "P$9") (pinfunction "INT2_P$9") (pintype "bidirectional"))
    )
    (net (code "30") (name "LSM9D-DEN-G") (class "Default")
      (node (ref "U$17") (pin "P$10") (pinfunction "DEN_G_P$10") (pintype "bidirectional"))
    )
    (net (code "31") (name "LSM9D-DRGY-G") (class "Default")
      (node (ref "U$17") (pin "P$12") (pinfunction "DRDY_G_P$12") (pintype "bidirectional"))
    )
    (net (code "32") (name "LSM9D-INT-G") (class "Default")
      (node (ref "U$11") (pin "P$15") (pinfunction "PC5_P$15") (pintype "bidirectional"))
      (node (ref "U$17") (pin "P$11") (pinfunction "INT_G_P$11") (pintype "bidirectional"))
    )
    (net (code "33") (name "LSM9D-INT1-XM") (class "Default")
      (node (ref "U$11") (pin "P$14") (pinfunction "PC6_P$14") (pintype "bidirectional"))
      (node (ref "U$17") (pin "P$13") (pinfunction "INT1_XM_P$13") (pintype "bidirectional"))
    )
    (net (code "34") (name "MISO-A") (class "Default")
      (node (ref "U$11") (pin "P$28") (pinfunction "PF0_P$28") (pintype "bidirectional"))
      (node (ref "U$14") (pin "P$8") (pinfunction "A7_P$8") (pintype "bidirectional"))
    )
    (net (code "35") (name "MISO-B") (class "Default")
      (node (ref "U$10") (pin "P$7") (pinfunction "MISO_P$7") (pintype "bidirectional"))
      (node (ref "U$14") (pin "P$13") (pinfunction "B7_P$13") (pintype "bidirectional"))
      (node (ref "U$17") (pin "P$22") (pinfunction "SDO_G_P$22") (pintype "bidirectional"))
      (node (ref "U$17") (pin "P$23") (pinfunction "SDO_XM_P$23") (pintype "bidirectional"))
      (node (ref "U$2") (pin "P$13") (pinfunction "MISO_P$13") (pintype "bidirectional"))
      (node (ref "U$3") (pin "P$4") (pinfunction "MISO_P$4") (pintype "bidirectional"))
      (node (ref "U$4") (pin "P$7") (pinfunction "MISO_P$7") (pintype "bidirectional"))
      (node (ref "U$6") (pin "P$7") (pinfunction "MISO_P$7") (pintype "bidirectional"))
      (node (ref "U$7") (pin "P$2") (pinfunction "DOUT_P$2") (pintype "bidirectional"))
      (node (ref "U$9") (pin "P$7") (pinfunction "MISO_P$7") (pintype "bidirectional"))
    )
    (net (code "36") (name "MOSI-A") (class "Default")
      (node (ref "U$11") (pin "P$29") (pinfunction "PF1_P$29") (pintype "bidirectional"))
      (node (ref "U$14") (pin "P$7") (pinfunction "A6_P$7") (pintype "bidirectional"))
    )
    (net (code "37") (name "MOSI-B") (class "Default")
      (node (ref "U$10") (pin "P$6") (pinfunction "MOSI_P$6") (pintype "bidirectional"))
      (node (ref "U$14") (pin "P$14") (pinfunction "B6_P$14") (pintype "bidirectional"))
      (node (ref "U$17") (pin "P$24") (pinfunction "SDA_P$24") (pintype "bidirectional"))
      (node (ref "U$2") (pin "P$12") (pinfunction "MOSI_P$12") (pintype "bidirectional"))
      (node (ref "U$3") (pin "P$3") (pinfunction "MOSI_P$3") (pintype "bidirectional"))
      (node (ref "U$4") (pin "P$6") (pinfunction "MOSI_P$6") (pintype "bidirectional"))
      (node (ref "U$6") (pin "P$6") (pinfunction "MOSI_P$6") (pintype "bidirectional"))
      (node (ref "U$7") (pin "P$3") (pinfunction "DIN_P$3") (pintype "bidirectional"))
      (node (ref "U$9") (pin "P$6") (pinfunction "MOSI_P$6") (pintype "bidirectional"))
    )
    (net (code "38") (name "N$25") (class "Default")
      (node (ref "C15") (pin "1") (pinfunction "1_1") (pintype "passive"))
      (node (ref "C16") (pin "1") (pinfunction "1_1") (pintype "passive"))
      (node (ref "U$5") (pin "P$1") (pinfunction "VDD_P$1") (pintype "bidirectional"))
    )
    (net (code "39") (name "Net-(BAT1-+)") (class "Default")
      (node (ref "BAT1") (pin "1") (pinfunction "+_1") (pintype "power_in"))
      (node (ref "S1") (pin "2") (pinfunction "P_2") (pintype "passive"))
    )
    (net (code "40") (name "Net-(C24-Pad2)") (class "Default")
      (node (ref "C24") (pin "2") (pinfunction "2_2") (pintype "passive"))
      (node (ref "R10") (pin "1") (pinfunction "1_1") (pintype "passive"))
    )
    (net (code "41") (name "Net-(C43-Pad1)") (class "Default")
      (node (ref "C43") (pin "1") (pinfunction "1_1") (pintype "passive"))
      (node (ref "R16") (pin "2") (pinfunction "2_2") (pintype "passive"))
      (node (ref "U$13") (pin "P$1") (pinfunction "P$1_P$1") (pintype "bidirectional"))
    )
    (net (code "42") (name "Net-(IC1A-IN)") (class "Default")
      (node (ref "IC1") (pin "1") (pinfunction "IN_1") (pintype "input"))
      (node (ref "IC2") (pin "1") (pinfunction "IN_1") (pintype "input"))
      (node (ref "IC3") (pin "1") (pinfunction "IN_1") (pintype "input"))
      (node (ref "IC4") (pin "1") (pinfunction "IN_1") (pintype "input"))
      (node (ref "S1") (pin "3") (pinfunction "S_3") (pintype "passive"))
    )
    (net (code "43") (name "Net-(LED1-PadA)") (class "Default")
      (node (ref "LED1") (pin "A") (pinfunction "A_A") (pintype "passive"))
      (node (ref "R7") (pin "1") (pinfunction "1_1") (pintype "passive"))
    )
    (net (code "44") (name "Net-(U$1-CAP-A)") (class "Default")
      (node (ref "C1") (pin "1") (pinfunction "1_1") (pintype "passive"))
      (node (ref "U$1") (pin "P$1") (pinfunction "CAP-A_P$1") (pintype "bidirectional"))
    )
    (net (code "45") (name "Net-(U$1-CAP-R)") (class "Default")
      (node (ref "C4") (pin "1") (pinfunction "1_1") (pintype "passive"))
      (node (ref "U$1") (pin "P$4") (pinfunction "CAP-R_P$4") (pintype "bidirectional"))
    )
    (net (code "46") (name "Net-(U$2-VREGD)") (class "Default")
      (node (ref "C7") (pin "1") (pinfunction "1_1") (pintype "passive"))
      (node (ref "U$2") (pin "P$16") (pinfunction "VREGD_P$16") (pintype "bidirectional"))
    )
    (net (code "47") (name "Net-(U$3-CAP)") (class "Default")
      (node (ref "C10") (pin "1") (pinfunction "1_1") (pintype "passive"))
      (node (ref "U$3") (pin "P$14") (pinfunction "CAP_P$14") (pintype "bidirectional"))
    )
    (net (code "48") (name "Net-(U$5-CAP)") (class "Default")
      (node (ref "C17") (pin "1") (pinfunction "1_1") (pintype "passive"))
      (node (ref "U$5") (pin "P$2") (pinfunction "CAP_P$2") (pintype "bidirectional"))
    )
    (net (code "49") (name "Net-(U$6-C1)") (class "Default")
      (node (ref "C18") (pin "1") (pinfunction "1_1") (pintype "passive"))
      (node (ref "U$6") (pin "P$15") (pinfunction "C1_P$15") (pintype "bidirectional"))
    )
    (net (code "50") (name "Net-(U$6-SETC)") (class "Default")
      (node (ref "C21") (pin "2") (pinfunction "2_2") (pintype "passive"))
      (node (ref "U$6") (pin "P$2") (pinfunction "SETC_P$2") (pintype "bidirectional"))
    )
    (net (code "51") (name "Net-(U$6-SETP)") (class "Default")
      (node (ref "C21") (pin "1") (pinfunction "1_1") (pintype "passive"))
      (node (ref "U$6") (pin "P$3") (pinfunction "SETP_P$3") (pintype "bidirectional"))
    )
    (net (code "52") (name "Net-(U$11-GNDX)") (class "Default")
      (node (ref "C41") (pin "2") (pinfunction "2_2") (pintype "passive"))
      (node (ref "C42") (pin "1") (pinfunction "1_1") (pintype "passive"))
      (node (ref "U$11") (pin "P$35") (pinfunction "GNDX_P$35") (pintype "bidirectional"))
    )
    (net (code "53") (name "Net-(U$11-OSC0)") (class "Default")
      (node (ref "C44") (pin "1") (pinfunction "1_1") (pintype "passive"))
      (node (ref "U$11") (pin "P$40") (pinfunction "OSC0_P$40") (pintype "bidirectional"))
      (node (ref "U$13") (pin "P$2") (pinfunction "P$2_P$2") (pintype "bidirectional"))
    )
    (net (code "54") (name "Net-(U$11-OSC1)") (class "Default")
      (node (ref "R16") (pin "1") (pinfunction "1_1") (pintype "passive"))
      (node (ref "U$11") (pin "P$41") (pinfunction "OSC1_P$41") (pintype "bidirectional"))
    )
    (net (code "55") (name "Net-(U$11-XOSC1)") (class "Default")
      (node (ref "C42") (pin "2") (pinfunction "2_2") (pintype "passive"))
      (node (ref "U$11") (pin "P$36") (pinfunction "XOSC1_P$36") (pintype "bidirectional"))
      (node (ref "U$12") (pin "P$2") (pinfunction "P$2_P$2") (pintype "bidirectional"))
    )
    (net (code "56") (name "Net-(U$11-XOSCO)") (class "Default")
      (node (ref "C41") (pin "1") (pinfunction "1_1") (pintype "passive"))
      (node (ref "U$11") (pin "P$34") (pinfunction "XOSCO_P$34") (pintype "bidirectional"))
      (node (ref "U$12") (pin "P$1") (pinfunction "P$1_P$1") (pintype "bidirectional"))
    )
    (net (code "57") (name "Net-(U$11-~{RST})") (class "Default")
      (node (ref "C30") (pin "2") (pinfunction "2_2") (pintype "passive"))
      (node (ref "R17") (pin "1") (pinfunction "1_1") (pintype "passive"))
      (node (ref "U$11") (pin "P$38") (pinfunction "~{RST}_P$38") (pintype "bidirectional"))
    )
    (net (code "58") (name "Net-(U$11-~{WAKE})") (class "Default")
      (node (ref "R15") (pin "1") (pinfunction "1_1") (pintype "passive"))
      (node (ref "U$11") (pin "P$32") (pinfunction "~{WAKE}_P$32") (pintype "bidirectional"))
    )
    (net (code "59") (name "Net-(U$17-C1_XM)") (class "Default")
      (node (ref "C48") (pin "1") (pinfunction "1_1") (pintype "passive"))
      (node (ref "U$17") (pin "P$7") (pinfunction "C1_XM_P$7") (pintype "bidirectional"))
    )
    (net (code "60") (name "Net-(U$17-SETC_XM)") (class "Default")
      (node (ref "C49") (pin "2") (pinfunction "2_2") (pintype "passive"))
      (node (ref "U$17") (pin "P$8") (pinfunction "SETC_XM_P$8") (pintype "bidirectional"))
    )
    (net (code "61") (name "Net-(U$17-SETP_XM)") (class "Default")
      (node (ref "C49") (pin "1") (pinfunction "1_1") (pintype "passive"))
      (node (ref "U$17") (pin "P$9") (pinfunction "SETP_XM_P$9") (pintype "bidirectional"))
    )
    (net (code "62") (name "RST_B") (class "Default")
      (node (ref "R5") (pin "1") (pinfunction "1_1") (pintype "passive"))
      (node (ref "U$2") (pin "P$4") (pinfunction "RST_B_P$4") (pintype "bidirectional"))
    )
    (net (code "63") (name "SCL-0") (class "Default")
      (node (ref "R1") (pin "1") (pinfunction "1_1") (pintype "passive"))
      (node (ref "TP6") (pin "P$1") (pinfunction "P$1_P$1") (pintype "bidirectional"))
      (node (ref "U$1") (pin "P$7") (pinfunction "SCL_P$7") (pintype "bidirectional"))
      (node (ref "U$11") (pin "P$47") (pinfunction "PB2_P$47") (pintype "bidirectional"))
      (node (ref "U$5") (pin "P$8") (pinfunction "SCL_P$8") (pintype "bidirectional"))
    )
    (net (code "64") (name "SCLK-A") (class "Default")
      (node (ref "U$11") (pin "P$30") (pinfunction "PF2_P$30") (pintype "bidirectional"))
      (node (ref "U$14") (pin "P$6") (pinfunction "A5_P$6") (pintype "bidirectional"))
    )
    (net (code "65") (name "SCLK-B") (class "Default")
      (node (ref "U$10") (pin "P$4") (pinfunction "SCLK_P$4") (pintype "bidirectional"))
      (node (ref "U$14") (pin "P$15") (pinfunction "B5_P$15") (pintype "bidirectional"))
      (node (ref "U$17") (pin "P$21") (pinfunction "SCL_P$21") (pintype "bidirectional"))
      (node (ref "U$2") (pin "P$11") (pinfunction "SCLK_P$11") (pintype "bidirectional"))
      (node (ref "U$3") (pin "P$2") (pinfunction "SCL_P$2") (pintype "bidirectional"))
      (node (ref "U$4") (pin "P$4") (pinfunction "SCL_P$4") (pintype "bidirectional"))
      (node (ref "U$6") (pin "P$4") (pinfunction "SCL_P$4") (pintype "bidirectional"))
      (node (ref "U$7") (pin "P$1") (pinfunction "SCLK_P$1") (pintype "bidirectional"))
      (node (ref "U$9") (pin "P$4") (pinfunction "SCL_P$4") (pintype "bidirectional"))
    )
    (net (code "66") (name "SD-CARD-INSERT") (class "Default")
      (node (ref "U$11") (pin "P$60") (pinfunction "PE5_P$60") (pintype "bidirectional"))
      (node (ref "U$18") (pin "P$8") (pinfunction "SWITCH2_P$8") (pintype "bidirectional"))
    )
    (net (code "67") (name "SD-CS") (class "Default")
      (node (ref "U$11") (pin "P$62") (pinfunction "PD1_P$62") (pintype "bidirectional"))
      (node (ref "U$18") (pin "P$2") (pinfunction "CS_P$2") (pintype "bidirectional"))
    )
    (net (code "68") (name "SD-MISO") (class "Default")
      (node (ref "U$11") (pin "P$63") (pinfunction "PD2_P$63") (pintype "bidirectional"))
      (node (ref "U$18") (pin "P$7") (pinfunction "D0_P$7") (pintype "bidirectional"))
    )
    (net (code "69") (name "SD-MOSI") (class "Default")
      (node (ref "U$11") (pin "P$64") (pinfunction "PD3_P$64") (pintype "bidirectional"))
      (node (ref "U$18") (pin "P$3") (pinfunction "DI_P$3") (pintype "bidirectional"))
    )
    (net (code "70") (name "SD-SCLK") (class "Default")
      (node (ref "U$11") (pin "P$61") (pinfunction "PD0_P$61") (pintype "bidirectional"))
      (node (ref "U$18") (pin "P$5") (pinfunction "SCLK_P$5") (pintype "bidirectional"))
    )
    (net (code "71") (name "SDA-0") (class "Default")
      (node (ref "R2") (pin "1") (pinfunction "1_1") (pintype "passive"))
      (node (ref "TP5") (pin "P$1") (pinfunction "P$1_P$1") (pintype "bidirectional"))
      (node (ref "U$1") (pin "P$6") (pinfunction "SDA_P$6") (pintype "bidirectional"))
      (node (ref "U$11") (pin "P$48") (pinfunction "PB3_P$48") (pintype "bidirectional"))
      (node (ref "U$5") (pin "P$7") (pinfunction "SDA_P$7") (pintype "bidirectional"))
    )
    (net (code "72") (name "SPI-ADDR0") (class "Default")
      (node (ref "U$11") (pin "P$22") (pinfunction "PA5_P$22") (pintype "bidirectional"))
      (node (ref "U$15") (pin "P$1") (pinfunction "A0_P$1") (pintype "bidirectional"))
    )
    (net (code "73") (name "SPI-ADDR1") (class "Default")
      (node (ref "U$11") (pin "P$21") (pinfunction "PA4_P$21") (pintype "bidirectional"))
      (node (ref "U$15") (pin "P$2") (pinfunction "A1_P$2") (pintype "bidirectional"))
    )
    (net (code "74") (name "SPI-ADDR2") (class "Default")
      (node (ref "U$11") (pin "P$20") (pinfunction "PA3_P$20") (pintype "bidirectional"))
      (node (ref "U$15") (pin "P$3") (pinfunction "A2_P$3") (pintype "bidirectional"))
    )
    (net (code "75") (name "SPI-ENABLE") (class "Default")
      (node (ref "U$11") (pin "P$31") (pinfunction "PF3_P$31") (pintype "bidirectional"))
      (node (ref "U$14") (pin "P$10") (pinfunction "OE_P$10") (pintype "bidirectional"))
    )
    (net (code "76") (name "SWCLK") (class "Default")
      (node (ref "U$11") (pin "P$52") (pinfunction "PC0_P$52") (pintype "bidirectional"))
      (node (ref "X3") (pin "4") (pinfunction "S_4") (pintype "passive"))
    )
    (net (code "77") (name "SWDIO") (class "Default")
      (node (ref "U$11") (pin "P$51") (pinfunction "PC1_P$51") (pintype "bidirectional"))
      (node (ref "X3") (pin "3") (pinfunction "S_3") (pintype "passive"))
    )
    (net (code "78") (name "SWO") (class "Default")
      (node (ref "U$11") (pin "P$49") (pinfunction "PC3_P$49") (pintype "bidirectional"))
      (node (ref "X3") (pin "1") (pinfunction "S_1") (pintype "passive"))
    )
    (net (code "79") (name "TDI") (class "Default")
      (node (ref "U$11") (pin "P$50") (pinfunction "PC2_P$50") (pintype "bidirectional"))
      (node (ref "X3") (pin "2") (pinfunction "S_2") (pintype "passive"))
    )
    (net (code "80") (name "U1RX") (class "Default")
      (node (ref "TP8") (pin "P$1") (pinfunction "P$1_P$1") (pintype "bidirectional"))
      (node (ref "U$11") (pin "P$45") (pinfunction "PB0_P$45") (pintype "bidirectional"))
    )
    (net (code "81") (name "U1TX") (class "Default")
      (node (ref "TP7") (pin "P$1") (pinfunction "P$1_P$1") (pintype "bidirectional"))
      (node (ref "U$11") (pin "P$46") (pinfunction "PB1_P$46") (pintype "bidirectional"))
    )
    (net (code "82") (name "unconnected-(S1-O-Pad1)") (class "Default")
      (node (ref "S1") (pin "1") (pinfunction "O_1") (pintype "passive"))
    )
    (net (code "83") (name "unconnected-(U$1-NC-PadP$3)") (class "Default")
      (node (ref "U$1") (pin "P$3") (pinfunction "NC_P$3") (pintype "bidirectional"))
    )
    (net (code "84") (name "unconnected-(U$2-INT2-PadP$2)") (class "Default")
      (node (ref "U$2") (pin "P$2") (pinfunction "INT2_P$2") (pintype "bidirectional"))
    )
    (net (code "85") (name "unconnected-(U$3-INT2-PadP$6)") (class "Default")
      (node (ref "U$3") (pin "P$6") (pinfunction "INT2_P$6") (pintype "bidirectional"))
    )
    (net (code "86") (name "unconnected-(U$4-NC$0-PadP$2)") (class "Default")
      (node (ref "U$4") (pin "P$2") (pinfunction "NC$0_P$2") (pintype "bidirectional"))
    )
    (net (code "87") (name "unconnected-(U$4-NC$1-PadP$3)") (class "Default")
      (node (ref "U$4") (pin "P$3") (pinfunction "NC$1_P$3") (pintype "bidirectional"))
    )
    (net (code "88") (name "unconnected-(U$5-INT2-PadP$5)") (class "Default")
      (node (ref "U$5") (pin "P$5") (pinfunction "INT2_P$5") (pintype "bidirectional"))
    )
    (net (code "89") (name "unconnected-(U$6-INT2-PadP$9)") (class "Default")
      (node (ref "U$6") (pin "P$9") (pinfunction "INT2_P$9") (pintype "bidirectional"))
    )
    (net (code "90") (name "unconnected-(U$8-NC-PadP$1)") (class "Default")
      (node (ref "U$8") (pin "P$1") (pinfunction "NC_P$1") (pintype "bidirectional"))
    )
    (net (code "91") (name "unconnected-(U$9-ADC1-PadP$16)") (class "Default")
      (node (ref "U$9") (pin "P$16") (pinfunction "ADC1_P$16") (pintype "bidirectional"))
    )
    (net (code "92") (name "unconnected-(U$9-ADC2-PadP$15)") (class "Default")
      (node (ref "U$9") (pin "P$15") (pinfunction "ADC2_P$15") (pintype "bidirectional"))
    )
    (net (code "93") (name "unconnected-(U$9-ADC3-PadP$13)") (class "Default")
      (node (ref "U$9") (pin "P$13") (pinfunction "ADC3_P$13") (pintype "bidirectional"))
    )
    (net (code "94") (name "unconnected-(U$9-INT2-PadP$9)") (class "Default")
      (node (ref "U$9") (pin "P$9") (pinfunction "INT2_P$9") (pintype "bidirectional"))
    )
    (net (code "95") (name "unconnected-(U$9-NC$0-PadP$2)") (class "Default")
      (node (ref "U$9") (pin "P$2") (pinfunction "NC$0_P$2") (pintype "bidirectional"))
    )
    (net (code "96") (name "unconnected-(U$9-NC$1-PadP$3)") (class "Default")
      (node (ref "U$9") (pin "P$3") (pinfunction "NC$1_P$3") (pintype "bidirectional"))
    )
    (net (code "97") (name "unconnected-(U$10-INT2-PadP$9)") (class "Default")
      (node (ref "U$10") (pin "P$9") (pinfunction "INT2_P$9") (pintype "bidirectional"))
    )
    (net (code "98") (name "unconnected-(U$10-NC$0-PadP$2)") (class "Default")
      (node (ref "U$10") (pin "P$2") (pinfunction "NC$0_P$2") (pintype "bidirectional"))
    )
    (net (code "99") (name "unconnected-(U$10-NC$1-PadP$15)") (class "Default")
      (node (ref "U$10") (pin "P$15") (pinfunction "NC$1_P$15") (pintype "bidirectional"))
    )
    (net (code "100") (name "unconnected-(U$10-RSVD$0-PadP$3)") (class "Default")
      (node (ref "U$10") (pin "P$3") (pinfunction "RSVD$0_P$3") (pintype "bidirectional"))
    )
    (net (code "101") (name "unconnected-(U$10-RSVD$1-PadP$5)") (class "Default")
      (node (ref "U$10") (pin "P$5") (pinfunction "RSVD$1_P$5") (pintype "bidirectional"))
    )
    (net (code "102") (name "unconnected-(U$10-RSVD$2-PadP$10)") (class "Default")
      (node (ref "U$10") (pin "P$10") (pinfunction "RSVD$2_P$10") (pintype "bidirectional"))
    )
    (net (code "103") (name "unconnected-(U$11-PA0-PadP$17)") (class "Default")
      (node (ref "U$11") (pin "P$17") (pinfunction "PA0_P$17") (pintype "bidirectional"))
    )
    (net (code "104") (name "unconnected-(U$11-PA1-PadP$18)") (class "Default")
      (node (ref "U$11") (pin "P$18") (pinfunction "PA1_P$18") (pintype "bidirectional"))
    )
    (net (code "105") (name "unconnected-(U$11-PA7-PadP$24)") (class "Default")
      (node (ref "U$11") (pin "P$24") (pinfunction "PA7_P$24") (pintype "bidirectional"))
    )
    (net (code "106") (name "unconnected-(U$11-PB4-PadP$58)") (class "Default")
      (node (ref "U$11") (pin "P$58") (pinfunction "PB4_P$58") (pintype "bidirectional"))
    )
    (net (code "107") (name "unconnected-(U$11-PB5-PadP$57)") (class "Default")
      (node (ref "U$11") (pin "P$57") (pinfunction "PB5_P$57") (pintype "bidirectional"))
    )
    (net (code "108") (name "unconnected-(U$11-PD4-PadP$43)") (class "Default")
      (node (ref "U$11") (pin "P$43") (pinfunction "PD4_P$43") (pintype "bidirectional"))
    )
    (net (code "109") (name "unconnected-(U$11-PD5-PadP$44)") (class "Default")
      (node (ref "U$11") (pin "P$44") (pinfunction "PD5_P$44") (pintype "bidirectional"))
    )
    (net (code "110") (name "unconnected-(U$11-PD6-PadP$53)") (class "Default")
      (node (ref "U$11") (pin "P$53") (pinfunction "PD6_P$53") (pintype "bidirectional"))
    )
    (net (code "111") (name "unconnected-(U$11-PE4-PadP$59)") (class "Default")
      (node (ref "U$11") (pin "P$59") (pinfunction "PE4_P$59") (pintype "bidirectional"))
    )
    (net (code "112") (name "unconnected-(U$11-~{HIB}-PadP$33)") (class "Default")
      (node (ref "U$11") (pin "P$33") (pinfunction "~{HIB}_P$33") (pintype "bidirectional"))
    )
    (net (code "113") (name "unconnected-(U$14-A1-PadP$1)") (class "Default")
      (node (ref "U$14") (pin "P$1") (pinfunction "A1_P$1") (pintype "bidirectional"))
    )
    (net (code "114") (name "unconnected-(U$14-A2-PadP$3)") (class "Default")
      (node (ref "U$14") (pin "P$3") (pinfunction "A2_P$3") (pintype "bidirectional"))
    )
    (net (code "115") (name "unconnected-(U$14-A3-PadP$4)") (class "Default")
      (node (ref "U$14") (pin "P$4") (pinfunction "A3_P$4") (pintype "bidirectional"))
    )
    (net (code "116") (name "unconnected-(U$14-A4-PadP$5)") (class "Default")
      (node (ref "U$14") (pin "P$5") (pinfunction "A4_P$5") (pintype "bidirectional"))
    )
    (net (code "117") (name "unconnected-(U$14-A8-PadP$9)") (class "Default")
      (node (ref "U$14") (pin "P$9") (pinfunction "A8_P$9") (pintype "bidirectional"))
    )
    (net (code "118") (name "unconnected-(U$14-B1-PadP$20)") (class "Default")
      (node (ref "U$14") (pin "P$20") (pinfunction "B1_P$20") (pintype "bidirectional"))
    )
    (net (code "119") (name "unconnected-(U$14-B2-PadP$18)") (class "Default")
      (node (ref "U$14") (pin "P$18") (pinfunction "B2_P$18") (pintype "bidirectional"))
    )
    (net (code "120") (name "unconnected-(U$14-B3-PadP$17)") (class "Default")
      (node (ref "U$14") (pin "P$17") (pinfunction "B3_P$17") (pintype "bidirectional"))
    )
    (net (code "121") (name "unconnected-(U$14-B4-PadP$16)") (class "Default")
      (node (ref "U$14") (pin "P$16") (pinfunction "B4_P$16") (pintype "bidirectional"))
    )
    (net (code "122") (name "unconnected-(U$14-B8-PadP$12)") (class "Default")
      (node (ref "U$14") (pin "P$12") (pinfunction "B8_P$12") (pintype "bidirectional"))
    )
    (net (code "123") (name "unconnected-(U$16-NC#0-PadP$1)") (class "Default")
      (node (ref "U$16") (pin "P$1") (pinfunction "NC#0_P$1") (pintype "bidirectional"))
    )
    (net (code "124") (name "unconnected-(U$16-NC#1-PadP$2)") (class "Default")
      (node (ref "U$16") (pin "P$2") (pinfunction "NC#1_P$2") (pintype "bidirectional"))
    )
    (net (code "125") (name "unconnected-(U$16-NC#2-PadP$5)") (class "Default")
      (node (ref "U$16") (pin "P$5") (pinfunction "NC#2_P$5") (pintype "bidirectional"))
    )
    (net (code "126") (name "unconnected-(U$17-INT2_XM-PadP$14)") (class "Default")
      (node (ref "U$17") (pin "P$14") (pinfunction "INT2_XM_P$14") (pintype "bidirectional"))
    )
    (net (code "127") (name "unconnected-(U$17-RES#0-PadP$1)") (class "Default")
      (node (ref "U$17") (pin "P$1") (pinfunction "RES#0_P$1") (pintype "bidirectional"))
    )
    (net (code "128") (name "unconnected-(U$18-GND#1-PadP$10)") (class "Default")
      (node (ref "U$18") (pin "P$10") (pinfunction "GND#1_P$10") (pintype "bidirectional"))
    )
    (net (code "129") (name "unconnected-(U$18-GND#2-PadP$11)") (class "Default")
      (node (ref "U$18") (pin "P$11") (pinfunction "GND#2_P$11") (pintype "bidirectional"))
    )
    (net (code "130") (name "unconnected-(U$18-GND#3-PadP$12)") (class "Default")
      (node (ref "U$18") (pin "P$12") (pinfunction "GND#3_P$12") (pintype "bidirectional"))
    )
    (net (code "131") (name "unconnected-(U$18-GND#4-PadP$13)") (class "Default")
      (node (ref "U$18") (pin "P$13") (pinfunction "GND#4_P$13") (pintype "bidirectional"))
    )
    (net (code "132") (name "unconnected-(U$18-RSV-PadP$1)") (class "Default")
      (node (ref "U$18") (pin "P$1") (pinfunction "RSV_P$1") (pintype "bidirectional"))
    )
  )
)
